# COM.net
KiCad netlist of a schematic drawn in Altium Designer
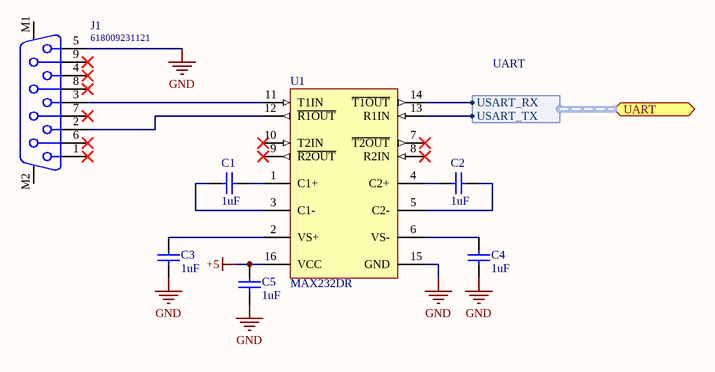
[diagram p0: COM.SchDoc]

(export (version "E")
  (design (tool "Eeschema 10.0.6"))
  (components
    (comp (ref "C1")
      (value "1uF")
      (footprint "CAP_0603i_1608m -N")
      (description "capacitor")
      (libsource (lib "IDSC std generic parts") (part "Cap"))
    )
    (comp (ref "C2")
      (value "1uF")
      (footprint "CAP_0603i_1608m -N")
      (description "capacitor")
      (libsource (lib "IDSC std generic parts") (part "Cap"))
    )
    (comp (ref "C3")
      (value "1uF")
      (footprint "CAP_0603i_1608m -N")
      (description "capacitor")
      (libsource (lib "IDSC std generic parts") (part "Cap"))
    )
    (comp (ref "C4")
      (value "1uF")
      (footprint "CAP_0603i_1608m -N")
      (description "capacitor")
      (libsource (lib "IDSC std generic parts") (part "Cap"))
    )
    (comp (ref "C5")
      (value "1uF")
      (footprint "CAP_0603i_1608m -N")
      (description "capacitor")
      (libsource (lib "IDSC std generic parts") (part "Cap"))
    )
    (comp (ref "J1")
      (value "618009231121")
      (footprint "618009231121")
      (description "Female PCB Connector with Hex Screw WR-DSUB, 8.08 mm, Angled, 9 pins")
      (fields (field (name "MANUFACTURER") "Wurth Elektronik") (field (name "PUBLISHER") "WurthElektronik"))
      (libsource (lib "Altium Content Vault") (part "WE-CN-2S-2F-D9"))
    )
    (comp (ref "U1")
      (value "MAX232DR")
      (footprint "D0016A_N")
      (description "Dual EIA-232 Driver / Receiver, 0 to 70 degC, 16-Pin SOIC (D), Green (RoHS & no Sb/Br)")
      (libsource (lib "Altium Content Vault") (part "TI-MAX232-SOIC_D-16"))
    )
  )
  (nets
    (net (code "2") (name "+5") (class "Default")
      (node (ref "C5") (pin "2") (pinfunction "2_2") (pintype "passive"))
      (node (ref "U1") (pin "16") (pinfunction "VCC_16") (pintype "power_in"))
    )
    (net (code "3") (name "/USART_RX") (class "Default")
      (node (ref "U1") (pin "14") (pinfunction "~{T1OUT}_14") (pintype "output"))
    )
    (net (code "4") (name "/USART_TX") (class "Default")
      (node (ref "U1") (pin "13") (pinfunction "R1IN_13") (pintype "input"))
    )
    (net (code "6") (name "GND") (class "Default")
      (node (ref "C3") (pin "1") (pinfunction "1_1") (pintype "passive"))
      (node (ref "C4") (pin "1") (pinfunction "1_1") (pintype "passive"))
      (node (ref "C5") (pin "1") (pinfunction "1_1") (pintype "passive"))
      (node (ref "J1") (pin "5") (pinfunction "5_5") (pintype "passive"))
      (node (ref "U1") (pin "15") (pinfunction "GND_15") (pintype "power_in"))
    )
    (net (code "7") (name "Net-(U1-C1+)") (class "Default")
      (node (ref "C1") (pin "1") (pinfunction "1_1") (pintype "passive"))
      (node (ref "U1") (pin "1") (pinfunction "C1+_1") (pintype "passive"))
    )
    (net (code "8") (name "Net-(U1-C1-)") (class "Default")
      (node (ref "C1") (pin "2") (pinfunction "2_2") (pintype "passive"))
      (node (ref "U1") (pin "3") (pinfunction "C1-_3") (pintype "passive"))
    )
    (net (code "9") (name "Net-(U1-C2+)") (class "Default")
      (node (ref "C2") (pin "2") (pinfunction "2_2") (pintype "passive"))
      (node (ref "U1") (pin "4") (pinfunction "C2+_4") (pintype "passive"))
    )
    (net (code "10") (name "Net-(U1-C2-)") (class "Default")
      (node (ref "C2") (pin "1") (pinfunction "1_1") (pintype "passive"))
      (node (ref "U1") (pin "5") (pinfunction "C2-_5") (pintype "passive"))
    )
    (net (code "11") (name "Net-(U1-T1IN)") (class "Default")
      (node (ref "J1") (pin "3") (pinfunction "3_3") (pintype "passive"))
      (node (ref "U1") (pin "11") (pinfunction "T1IN_11") (pintype "input"))
    )
    (net (code "12") (name "Net-(U1-VS+)") (class "Default")
      (node (ref "C3") (pin "2") (pinfunction "2_2") (pintype "passive"))
      (node (ref "U1") (pin "2") (pinfunction "VS+_2") (pintype "power_in"))
    )
    (net (code "13") (name "Net-(U1-VS-)") (class "Default")
      (node (ref "C4") (pin "2") (pinfunction "2_2") (pintype "passive"))
      (node (ref "U1") (pin "6") (pinfunction "VS-_6") (pintype "power_in"))
    )
    (net (code "14") (name "Net-(U1-~{R1OUT})") (class "Default")
      (node (ref "J1") (pin "2") (pinfunction "2_2") (pintype "passive"))
      (node (ref "U1") (pin "12") (pinfunction "~{R1OUT}_12") (pintype "output"))
    )
    (net (code "15") (name "unconnected-(J1-Pad1)") (class "Default")
      (node (ref "J1") (pin "1") (pinfunction "1_1") (pintype "passive+no_connect"))
    )
    (net (code "16") (name "unconnected-(J1-Pad4)") (class "Default")
      (node (ref "J1") (pin "4") (pinfunction "4_4") (pintype "passive+no_connect"))
    )
    (net (code "17") (name "unconnected-(J1-Pad6)") (class "Default")
      (node (ref "J1") (pin "6") (pinfunction "6_6") (pintype "passive+no_connect"))
    )
    (net (code "18") (name "unconnected-(J1-Pad7)") (class "Default")
      (node (ref "J1") (pin "7") (pinfunction "7_7") (pintype "passive+no_connect"))
    )
    (net (code "19") (name "unconnected-(J1-Pad8)") (class "Default")
      (node (ref "J1") (pin "8") (pinfunction "8_8") (pintype "passive+no_connect"))
    )
    (net (code "20") (name "unconnected-(J1-Pad9)") (class "Default")
      (node (ref "J1") (pin "9") (pinfunction "9_9") (pintype "passive+no_connect"))
    )
    (net (code "21") (name "unconnected-(J1-PadM1)") (class "Default")
      (node (ref "J1") (pin "M1") (pinfunction "M1_M1") (pintype "passive"))
    )
    (net (code "22") (name "unconnected-(J1-PadM2)") (class "Default")
      (node (ref "J1") (pin "M2") (pinfunction "M2_M2") (pintype "passive"))
    )
    (net (code "23") (name "unconnected-(U1-R2IN-Pad8)") (class "Default")
      (node (ref "U1") (pin "8") (pinfunction "R2IN_8") (pintype "input+no_connect"))
    )
    (net (code "24") (name "unconnected-(U1-T2IN-Pad10)") (class "Default")
      (node (ref "U1") (pin "10") (pinfunction "T2IN_10") (pintype "input+no_connect"))
    )
    (net (code "25") (name "unconnected-(U1-~{R2OUT}-Pad9)") (class "Default")
      (node (ref "U1") (pin "9") (pinfunction "~{R2OUT}_9") (pintype "output+no_connect"))
    )
    (net (code "26") (name "unconnected-(U1-~{T2OUT}-Pad7)") (class "Default")
      (node (ref "U1") (pin "7") (pinfunction "~{T2OUT}_7") (pintype "output+no_connect"))
    )
  )
)
